# multiEncoder.net
KiCad netlist of a schematic drawn in EAGLE
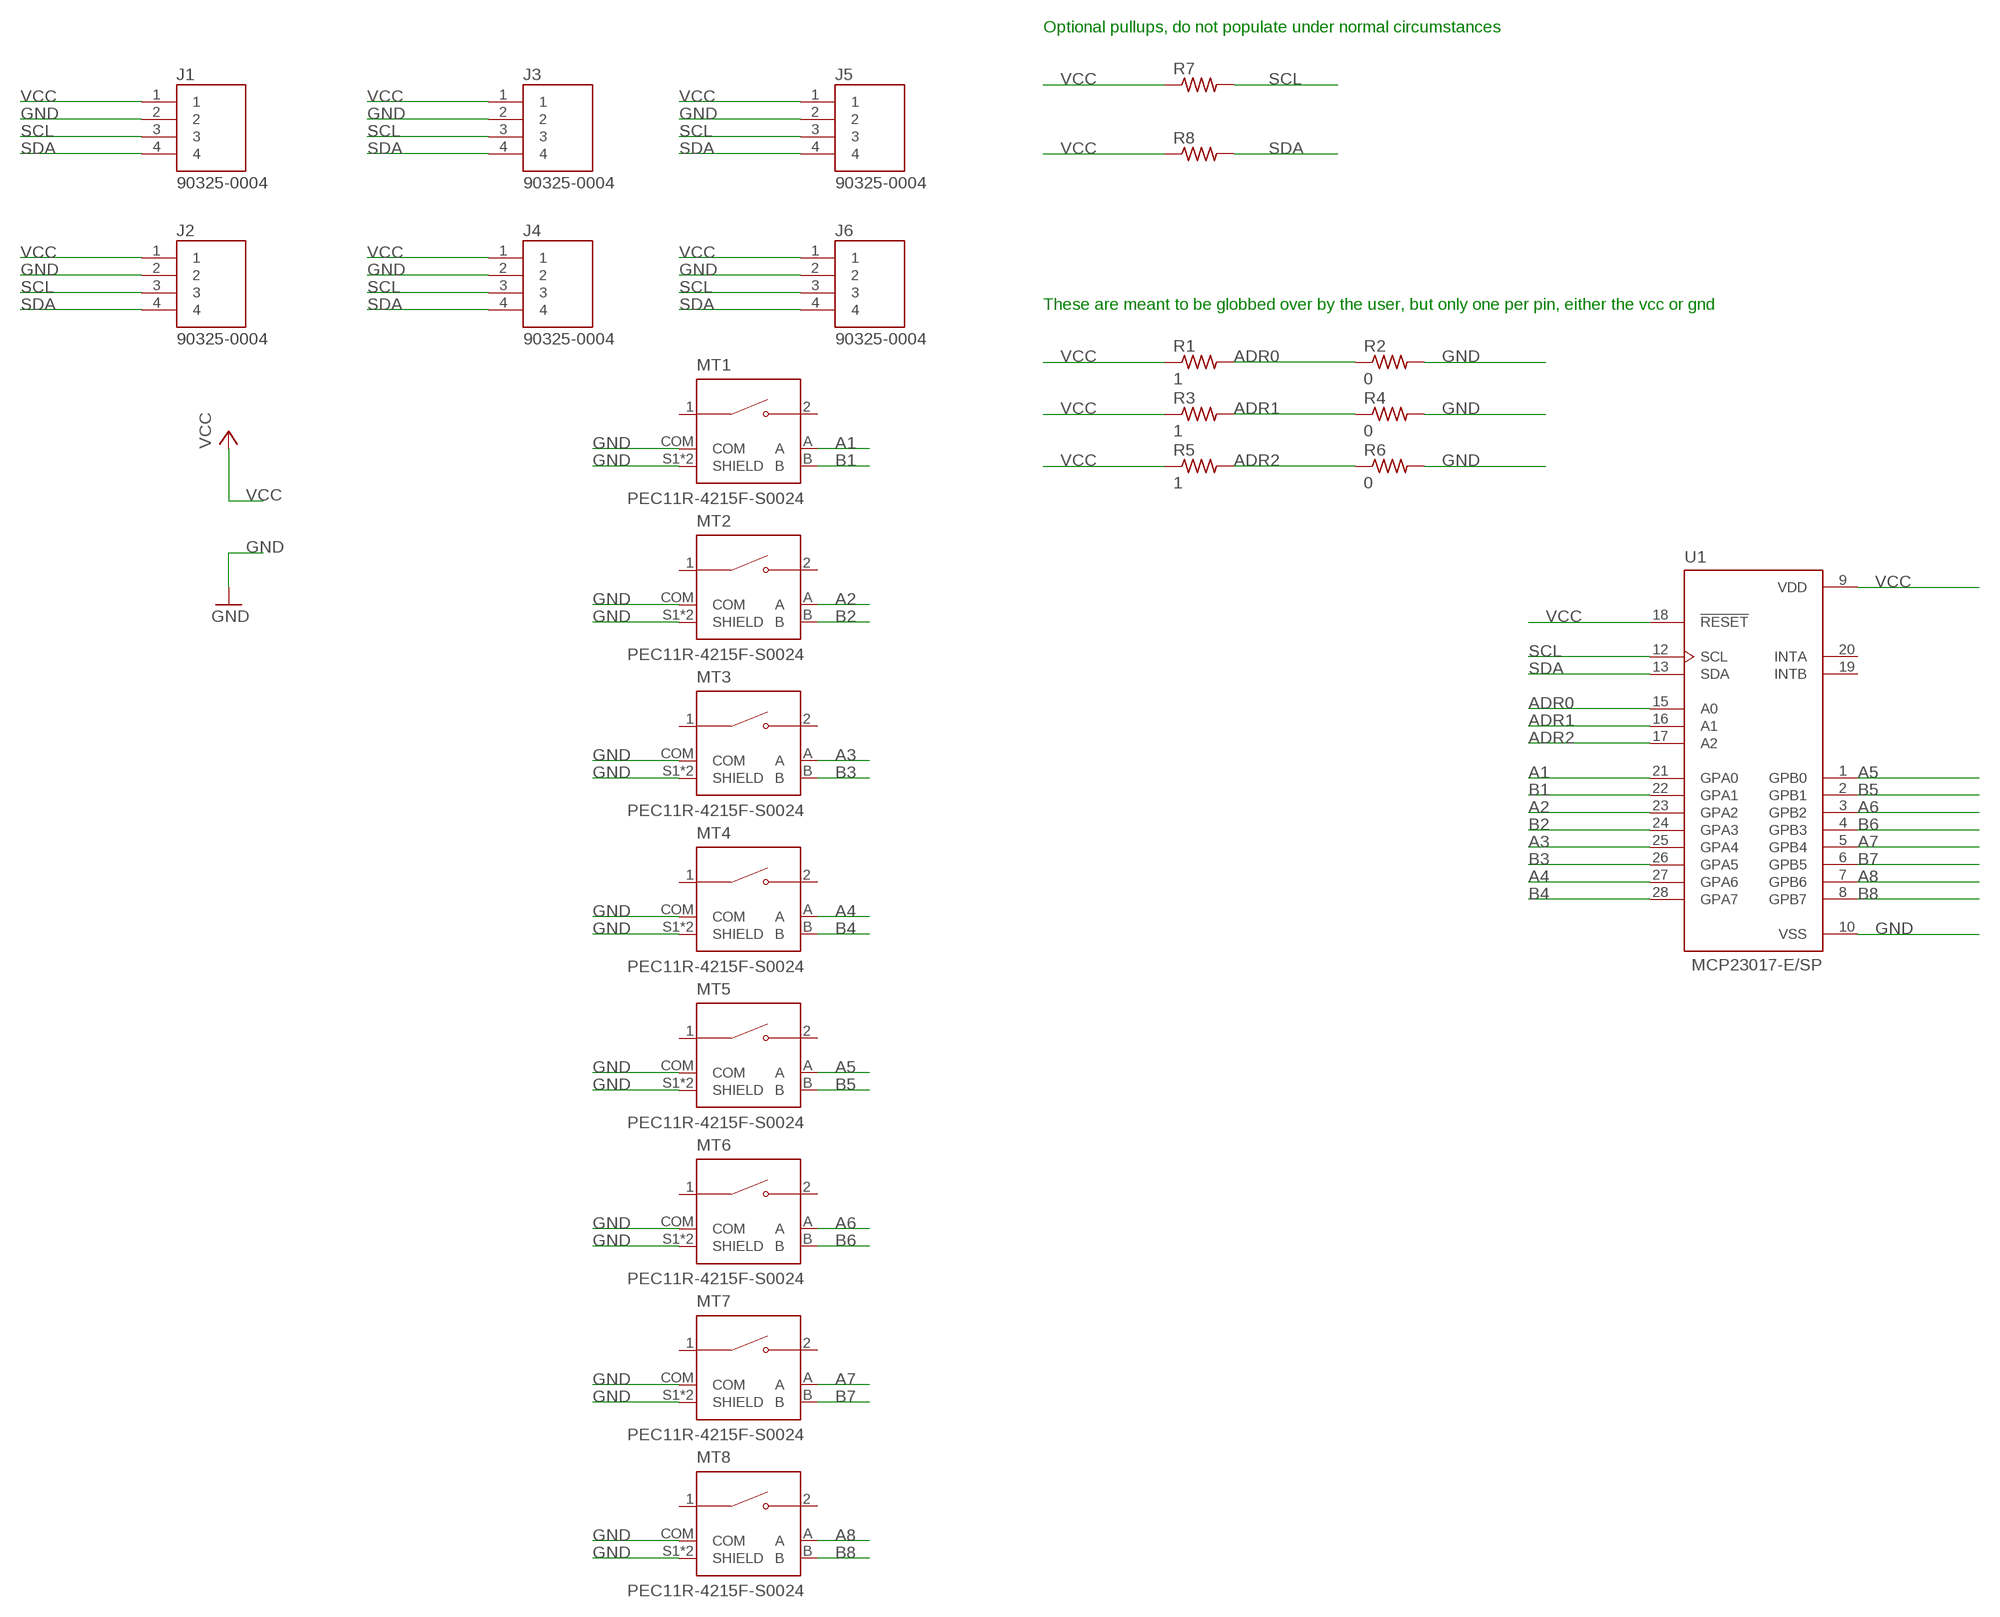
[diagram p0: schematic, sheet 1]

(export (version "E")
  (design (tool "Eeschema 10.0.6"))
  (components
    (comp (ref "J1")
      (value "90325-0004")
      (footprint "eagle-import:MOLEX_90325-0004")
      (fields (field (name "MF") "Molex"))
      (libsource (lib "eagle-import") (part "90325-0004"))
    )
    (comp (ref "J2")
      (value "90325-0004")
      (footprint "eagle-import:MOLEX_90325-0004")
      (fields (field (name "MF") "Molex"))
      (libsource (lib "eagle-import") (part "90325-0004"))
    )
    (comp (ref "J3")
      (value "90325-0004")
      (footprint "eagle-import:MOLEX_90325-0004")
      (fields (field (name "MF") "Molex"))
      (libsource (lib "eagle-import") (part "90325-0004"))
    )
    (comp (ref "J4")
      (value "90325-0004")
      (footprint "eagle-import:MOLEX_90325-0004")
      (fields (field (name "MF") "Molex"))
      (libsource (lib "eagle-import") (part "90325-0004"))
    )
    (comp (ref "J5")
      (value "90325-0004")
      (footprint "eagle-import:MOLEX_90325-0004")
      (fields (field (name "MF") "Molex"))
      (libsource (lib "eagle-import") (part "90325-0004"))
    )
    (comp (ref "J6")
      (value "90325-0004")
      (footprint "eagle-import:MOLEX_90325-0004")
      (fields (field (name "MF") "Molex"))
      (libsource (lib "eagle-import") (part "90325-0004"))
    )
    (comp (ref "MT1")
      (value "PEC11R-4215F-S0024")
      (footprint "eagle-import:XDCR_PEC11R-4215F-S0024")
      (fields (field (name "MF") "Bourns"))
      (libsource (lib "eagle-import") (part "PEC11R-4215F-S0024"))
    )
    (comp (ref "MT2")
      (value "PEC11R-4215F-S0024")
      (footprint "eagle-import:XDCR_PEC11R-4215F-S0024")
      (fields (field (name "MF") "Bourns"))
      (libsource (lib "eagle-import") (part "PEC11R-4215F-S0024"))
    )
    (comp (ref "MT3")
      (value "PEC11R-4215F-S0024")
      (footprint "eagle-import:XDCR_PEC11R-4215F-S0024")
      (fields (field (name "MF") "Bourns"))
      (libsource (lib "eagle-import") (part "PEC11R-4215F-S0024"))
    )
    (comp (ref "MT4")
      (value "PEC11R-4215F-S0024")
      (footprint "eagle-import:XDCR_PEC11R-4215F-S0024")
      (fields (field (name "MF") "Bourns"))
      (libsource (lib "eagle-import") (part "PEC11R-4215F-S0024"))
    )
    (comp (ref "MT5")
      (value "PEC11R-4215F-S0024")
      (footprint "eagle-import:XDCR_PEC11R-4215F-S0024")
      (fields (field (name "MF") "Bourns"))
      (libsource (lib "eagle-import") (part "PEC11R-4215F-S0024"))
    )
    (comp (ref "MT6")
      (value "PEC11R-4215F-S0024")
      (footprint "eagle-import:XDCR_PEC11R-4215F-S0024")
      (fields (field (name "MF") "Bourns"))
      (libsource (lib "eagle-import") (part "PEC11R-4215F-S0024"))
    )
    (comp (ref "MT7")
      (value "PEC11R-4215F-S0024")
      (footprint "eagle-import:XDCR_PEC11R-4215F-S0024")
      (fields (field (name "MF") "Bourns"))
      (libsource (lib "eagle-import") (part "PEC11R-4215F-S0024"))
    )
    (comp (ref "MT8")
      (value "PEC11R-4215F-S0024")
      (footprint "eagle-import:XDCR_PEC11R-4215F-S0024")
      (fields (field (name "MF") "Bourns"))
      (libsource (lib "eagle-import") (part "PEC11R-4215F-S0024"))
    )
    (comp (ref "R1")
      (value "1")
      (footprint "eagle-import:R0805")
      (libsource (lib "eagle-import") (part "R-US_R0805"))
    )
    (comp (ref "R2")
      (value "0")
      (footprint "eagle-import:R0805")
      (libsource (lib "eagle-import") (part "R-US_R0805"))
    )
    (comp (ref "R3")
      (value "1")
      (footprint "eagle-import:R0805")
      (libsource (lib "eagle-import") (part "R-US_R0805"))
    )
    (comp (ref "R4")
      (value "0")
      (footprint "eagle-import:R0805")
      (libsource (lib "eagle-import") (part "R-US_R0805"))
    )
    (comp (ref "R5")
      (value "1")
      (footprint "eagle-import:R0805")
      (libsource (lib "eagle-import") (part "R-US_R0805"))
    )
    (comp (ref "R6")
      (value "0")
      (footprint "eagle-import:R0805")
      (libsource (lib "eagle-import") (part "R-US_R0805"))
    )
    (comp (ref "R7")
      (value "1K")
      (footprint "eagle-import:R0805")
      (libsource (lib "eagle-import") (part "R-US_R0805"))
    )
    (comp (ref "R8")
      (value "1K")
      (footprint "eagle-import:R0805")
      (libsource (lib "eagle-import") (part "R-US_R0805"))
    )
    (comp (ref "U1")
      (value "MCP23017-E/SP")
      (footprint "eagle-import:DIP787W45P254L3556H508Q28")
      (fields (field (name "MF") "Microchip"))
      (libsource (lib "eagle-import") (part "MCP23017-E/SP"))
    )
  )
  (nets
    (net (code "1") (name "/A1") (class "Default")
      (node (ref "MT1") (pin "A") (pinfunction "A_A") (pintype "passive"))
      (node (ref "U1") (pin "21") (pinfunction "GPA0_21") (pintype "bidirectional"))
    )
    (net (code "2") (name "/A2") (class "Default")
      (node (ref "MT2") (pin "A") (pinfunction "A_A") (pintype "passive"))
      (node (ref "U1") (pin "23") (pinfunction "GPA2_23") (pintype "bidirectional"))
    )
    (net (code "3") (name "/A3") (class "Default")
      (node (ref "MT3") (pin "A") (pinfunction "A_A") (pintype "passive"))
      (node (ref "U1") (pin "25") (pinfunction "GPA4_25") (pintype "bidirectional"))
    )
    (net (code "4") (name "/A4") (class "Default")
      (node (ref "MT4") (pin "A") (pinfunction "A_A") (pintype "passive"))
      (node (ref "U1") (pin "27") (pinfunction "GPA6_27") (pintype "bidirectional"))
    )
    (net (code "5") (name "/A5") (class "Default")
      (node (ref "MT5") (pin "A") (pinfunction "A_A") (pintype "passive"))
      (node (ref "U1") (pin "1") (pinfunction "GPB0_1") (pintype "bidirectional"))
    )
    (net (code "6") (name "/A6") (class "Default")
      (node (ref "MT6") (pin "A") (pinfunction "A_A") (pintype "passive"))
      (node (ref "U1") (pin "3") (pinfunction "GPB2_3") (pintype "bidirectional"))
    )
    (net (code "7") (name "/A7") (class "Default")
      (node (ref "MT7") (pin "A") (pinfunction "A_A") (pintype "passive"))
      (node (ref "U1") (pin "5") (pinfunction "GPB4_5") (pintype "bidirectional"))
    )
    (net (code "8") (name "/A8") (class "Default")
      (node (ref "MT8") (pin "A") (pinfunction "A_A") (pintype "passive"))
      (node (ref "U1") (pin "7") (pinfunction "GPB6_7") (pintype "bidirectional"))
    )
    (net (code "9") (name "/ADR0") (class "Default")
      (node (ref "R1") (pin "2") (pinfunction "2_2") (pintype "passive"))
      (node (ref "R2") (pin "1") (pinfunction "1_1") (pintype "passive"))
      (node (ref "U1") (pin "15") (pinfunction "A0_15") (pintype "input"))
    )
    (net (code "10") (name "/ADR1") (class "Default")
      (node (ref "R3") (pin "2") (pinfunction "2_2") (pintype "passive"))
      (node (ref "R4") (pin "1") (pinfunction "1_1") (pintype "passive"))
      (node (ref "U1") (pin "16") (pinfunction "A1_16") (pintype "input"))
    )
    (net (code "11") (name "/ADR2") (class "Default")
      (node (ref "R5") (pin "2") (pinfunction "2_2") (pintype "passive"))
      (node (ref "R6") (pin "1") (pinfunction "1_1") (pintype "passive"))
      (node (ref "U1") (pin "17") (pinfunction "A2_17") (pintype "input"))
    )
    (net (code "12") (name "/B1") (class "Default")
      (node (ref "MT1") (pin "B") (pinfunction "B_B") (pintype "passive"))
      (node (ref "U1") (pin "22") (pinfunction "GPA1_22") (pintype "bidirectional"))
    )
    (net (code "13") (name "/B2") (class "Default")
      (node (ref "MT2") (pin "B") (pinfunction "B_B") (pintype "passive"))
      (node (ref "U1") (pin "24") (pinfunction "GPA3_24") (pintype "bidirectional"))
    )
    (net (code "14") (name "/B3") (class "Default")
      (node (ref "MT3") (pin "B") (pinfunction "B_B") (pintype "passive"))
      (node (ref "U1") (pin "26") (pinfunction "GPA5_26") (pintype "bidirectional"))
    )
    (net (code "15") (name "/B4") (class "Default")
      (node (ref "MT4") (pin "B") (pinfunction "B_B") (pintype "passive"))
      (node (ref "U1") (pin "28") (pinfunction "GPA7_28") (pintype "bidirectional"))
    )
    (net (code "16") (name "/B5") (class "Default")
      (node (ref "MT5") (pin "B") (pinfunction "B_B") (pintype "passive"))
      (node (ref "U1") (pin "2") (pinfunction "GPB1_2") (pintype "bidirectional"))
    )
    (net (code "17") (name "/B6") (class "Default")
      (node (ref "MT6") (pin "B") (pinfunction "B_B") (pintype "passive"))
      (node (ref "U1") (pin "4") (pinfunction "GPB3_4") (pintype "bidirectional"))
    )
    (net (code "18") (name "/B7") (class "Default")
      (node (ref "MT7") (pin "B") (pinfunction "B_B") (pintype "passive"))
      (node (ref "U1") (pin "6") (pinfunction "GPB5_6") (pintype "bidirectional"))
    )
    (net (code "19") (name "/B8") (class "Default")
      (node (ref "MT8") (pin "B") (pinfunction "B_B") (pintype "passive"))
      (node (ref "U1") (pin "8") (pinfunction "GPB7_8") (pintype "bidirectional"))
    )
    (net (code "20") (name "/SCL") (class "Default")
      (node (ref "J1") (pin "3") (pinfunction "3_3") (pintype "passive"))
      (node (ref "J2") (pin "3") (pinfunction "3_3") (pintype "passive"))
      (node (ref "J3") (pin "3") (pinfunction "3_3") (pintype "passive"))
      (node (ref "J4") (pin "3") (pinfunction "3_3") (pintype "passive"))
      (node (ref "J5") (pin "3") (pinfunction "3_3") (pintype "passive"))
      (node (ref "J6") (pin "3") (pinfunction "3_3") (pintype "passive"))
      (node (ref "R7") (pin "2") (pinfunction "2_2") (pintype "passive"))
      (node (ref "U1") (pin "12") (pinfunction "SCL_12") (pintype "input"))
    )
    (net (code "21") (name "/SDA") (class "Default")
      (node (ref "J1") (pin "4") (pinfunction "4_4") (pintype "passive"))
      (node (ref "J2") (pin "4") (pinfunction "4_4") (pintype "passive"))
      (node (ref "J3") (pin "4") (pinfunction "4_4") (pintype "passive"))
      (node (ref "J4") (pin "4") (pinfunction "4_4") (pintype "passive"))
      (node (ref "J5") (pin "4") (pinfunction "4_4") (pintype "passive"))
      (node (ref "J6") (pin "4") (pinfunction "4_4") (pintype "passive"))
      (node (ref "R8") (pin "2") (pinfunction "2_2") (pintype "passive"))
      (node (ref "U1") (pin "13") (pinfunction "SDA_13") (pintype "bidirectional"))
    )
    (net (code "22") (name "GND") (class "Default")
      (node (ref "J1") (pin "2") (pinfunction "2_2") (pintype "passive"))
      (node (ref "J2") (pin "2") (pinfunction "2_2") (pintype "passive"))
      (node (ref "J3") (pin "2") (pinfunction "2_2") (pintype "passive"))
      (node (ref "J4") (pin "2") (pinfunction "2_2") (pintype "passive"))
      (node (ref "J5") (pin "2") (pinfunction "2_2") (pintype "passive"))
      (node (ref "J6") (pin "2") (pinfunction "2_2") (pintype "passive"))
      (node (ref "MT1") (pin "COM") (pinfunction "COM_COM") (pintype "passive"))
      (node (ref "MT1") (pin "S1") (pinfunction "SHIELD_S1") (pintype "passive"))
      (node (ref "MT1") (pin "S2") (pinfunction "SHIELD_S2") (pintype "passive"))
      (node (ref "MT2") (pin "COM") (pinfunction "COM_COM") (pintype "passive"))
      (node (ref "MT2") (pin "S1") (pinfunction "SHIELD_S1") (pintype "passive"))
      (node (ref "MT2") (pin "S2") (pinfunction "SHIELD_S2") (pintype "passive"))
      (node (ref "MT3") (pin "COM") (pinfunction "COM_COM") (pintype "passive"))
      (node (ref "MT3") (pin "S1") (pinfunction "SHIELD_S1") (pintype "passive"))
      (node (ref "MT3") (pin "S2") (pinfunction "SHIELD_S2") (pintype "passive"))
      (node (ref "MT4") (pin "COM") (pinfunction "COM_COM") (pintype "passive"))
      (node (ref "MT4") (pin "S1") (pinfunction "SHIELD_S1") (pintype "passive"))
      (node (ref "MT4") (pin "S2") (pinfunction "SHIELD_S2") (pintype "passive"))
      (node (ref "MT5") (pin "COM") (pinfunction "COM_COM") (pintype "passive"))
      (node (ref "MT5") (pin "S1") (pinfunction "SHIELD_S1") (pintype "passive"))
      (node (ref "MT5") (pin "S2") (pinfunction "SHIELD_S2") (pintype "passive"))
      (node (ref "MT6") (pin "COM") (pinfunction "COM_COM") (pintype "passive"))
      (node (ref "MT6") (pin "S1") (pinfunction "SHIELD_S1") (pintype "passive"))
      (node (ref "MT6") (pin "S2") (pinfunction "SHIELD_S2") (pintype "passive"))
      (node (ref "MT7") (pin "COM") (pinfunction "COM_COM") (pintype "passive"))
      (node (ref "MT7") (pin "S1") (pinfunction "SHIELD_S1") (pintype "passive"))
      (node (ref "MT7") (pin "S2") (pinfunction "SHIELD_S2") (pintype "passive"))
      (node (ref "MT8") (pin "COM") (pinfunction "COM_COM") (pintype "passive"))
      (node (ref "MT8") (pin "S1") (pinfunction "SHIELD_S1") (pintype "passive"))
      (node (ref "MT8") (pin "S2") (pinfunction "SHIELD_S2") (pintype "passive"))
      (node (ref "R2") (pin "2") (pinfunction "2_2") (pintype "passive"))
      (node (ref "R4") (pin "2") (pinfunction "2_2") (pintype "passive"))
      (node (ref "R6") (pin "2") (pinfunction "2_2") (pintype "passive"))
      (node (ref "U1") (pin "10") (pinfunction "VSS_10") (pintype "power_in"))
    )
    (net (code "23") (name "VCC") (class "Default")
      (node (ref "J1") (pin "1") (pinfunction "1_1") (pintype "passive"))
      (node (ref "J2") (pin "1") (pinfunction "1_1") (pintype "passive"))
      (node (ref "J3") (pin "1") (pinfunction "1_1") (pintype "passive"))
      (node (ref "J4") (pin "1") (pinfunction "1_1") (pintype "passive"))
      (node (ref "J5") (pin "1") (pinfunction "1_1") (pintype "passive"))
      (node (ref "J6") (pin "1") (pinfunction "1_1") (pintype "passive"))
      (node (ref "R1") (pin "1") (pinfunction "1_1") (pintype "passive"))
      (node (ref "R3") (pin "1") (pinfunction "1_1") (pintype "passive"))
      (node (ref "R5") (pin "1") (pinfunction "1_1") (pintype "passive"))
      (node (ref "R7") (pin "1") (pinfunction "1_1") (pintype "passive"))
      (node (ref "R8") (pin "1") (pinfunction "1_1") (pintype "passive"))
      (node (ref "U1") (pin "18") (pinfunction "~{RESET}_18") (pintype "input"))
      (node (ref "U1") (pin "9") (pinfunction "VDD_9") (pintype "power_in"))
    )
    (net (code "24") (name "unconnected-(MT1-Pad1)") (class "Default")
      (node (ref "MT1") (pin "1") (pinfunction "1_1") (pintype "passive"))
    )
    (net (code "25") (name "unconnected-(MT1-Pad2)") (class "Default")
      (node (ref "MT1") (pin "2") (pinfunction "2_2") (pintype "passive"))
    )
    (net (code "26") (name "unconnected-(MT2-Pad1)") (class "Default")
      (node (ref "MT2") (pin "1") (pinfunction "1_1") (pintype "passive"))
    )
    (net (code "27") (name "unconnected-(MT2-Pad2)") (class "Default")
      (node (ref "MT2") (pin "2") (pinfunction "2_2") (pintype "passive"))
    )
    (net (code "28") (name "unconnected-(MT3-Pad1)") (class "Default")
      (node (ref "MT3") (pin "1") (pinfunction "1_1") (pintype "passive"))
    )
    (net (code "29") (name "unconnected-(MT3-Pad2)") (class "Default")
      (node (ref "MT3") (pin "2") (pinfunction "2_2") (pintype "passive"))
    )
    (net (code "30") (name "unconnected-(MT4-Pad1)") (class "Default")
      (node (ref "MT4") (pin "1") (pinfunction "1_1") (pintype "passive"))
    )
    (net (code "31") (name "unconnected-(MT4-Pad2)") (class "Default")
      (node (ref "MT4") (pin "2") (pinfunction "2_2") (pintype "passive"))
    )
    (net (code "32") (name "unconnected-(MT5-Pad1)") (class "Default")
      (node (ref "MT5") (pin "1") (pinfunction "1_1") (pintype "passive"))
    )
    (net (code "33") (name "unconnected-(MT5-Pad2)") (class "Default")
      (node (ref "MT5") (pin "2") (pinfunction "2_2") (pintype "passive"))
    )
    (net (code "34") (name "unconnected-(MT6-Pad1)") (class "Default")
      (node (ref "MT6") (pin "1") (pinfunction "1_1") (pintype "passive"))
    )
    (net (code "35") (name "unconnected-(MT6-Pad2)") (class "Default")
      (node (ref "MT6") (pin "2") (pinfunction "2_2") (pintype "passive"))
    )
    (net (code "36") (name "unconnected-(MT7-Pad1)") (class "Default")
      (node (ref "MT7") (pin "1") (pinfunction "1_1") (pintype "passive"))
    )
    (net (code "37") (name "unconnected-(MT7-Pad2)") (class "Default")
      (node (ref "MT7") (pin "2") (pinfunction "2_2") (pintype "passive"))
    )
    (net (code "38") (name "unconnected-(MT8-Pad1)") (class "Default")
      (node (ref "MT8") (pin "1") (pinfunction "1_1") (pintype "passive"))
    )
    (net (code "39") (name "unconnected-(MT8-Pad2)") (class "Default")
      (node (ref "MT8") (pin "2") (pinfunction "2_2") (pintype "passive"))
    )
    (net (code "40") (name "unconnected-(U1-INTA-Pad20)") (class "Default")
      (node (ref "U1") (pin "20") (pinfunction "INTA_20") (pintype "output"))
    )
    (net (code "41") (name "unconnected-(U1-INTB-Pad19)") (class "Default")
      (node (ref "U1") (pin "19") (pinfunction "INTB_19") (pintype "output"))
    )
  )
)
